# InkTime_Schematic.net
KiCad netlist of a schematic drawn in EAGLE
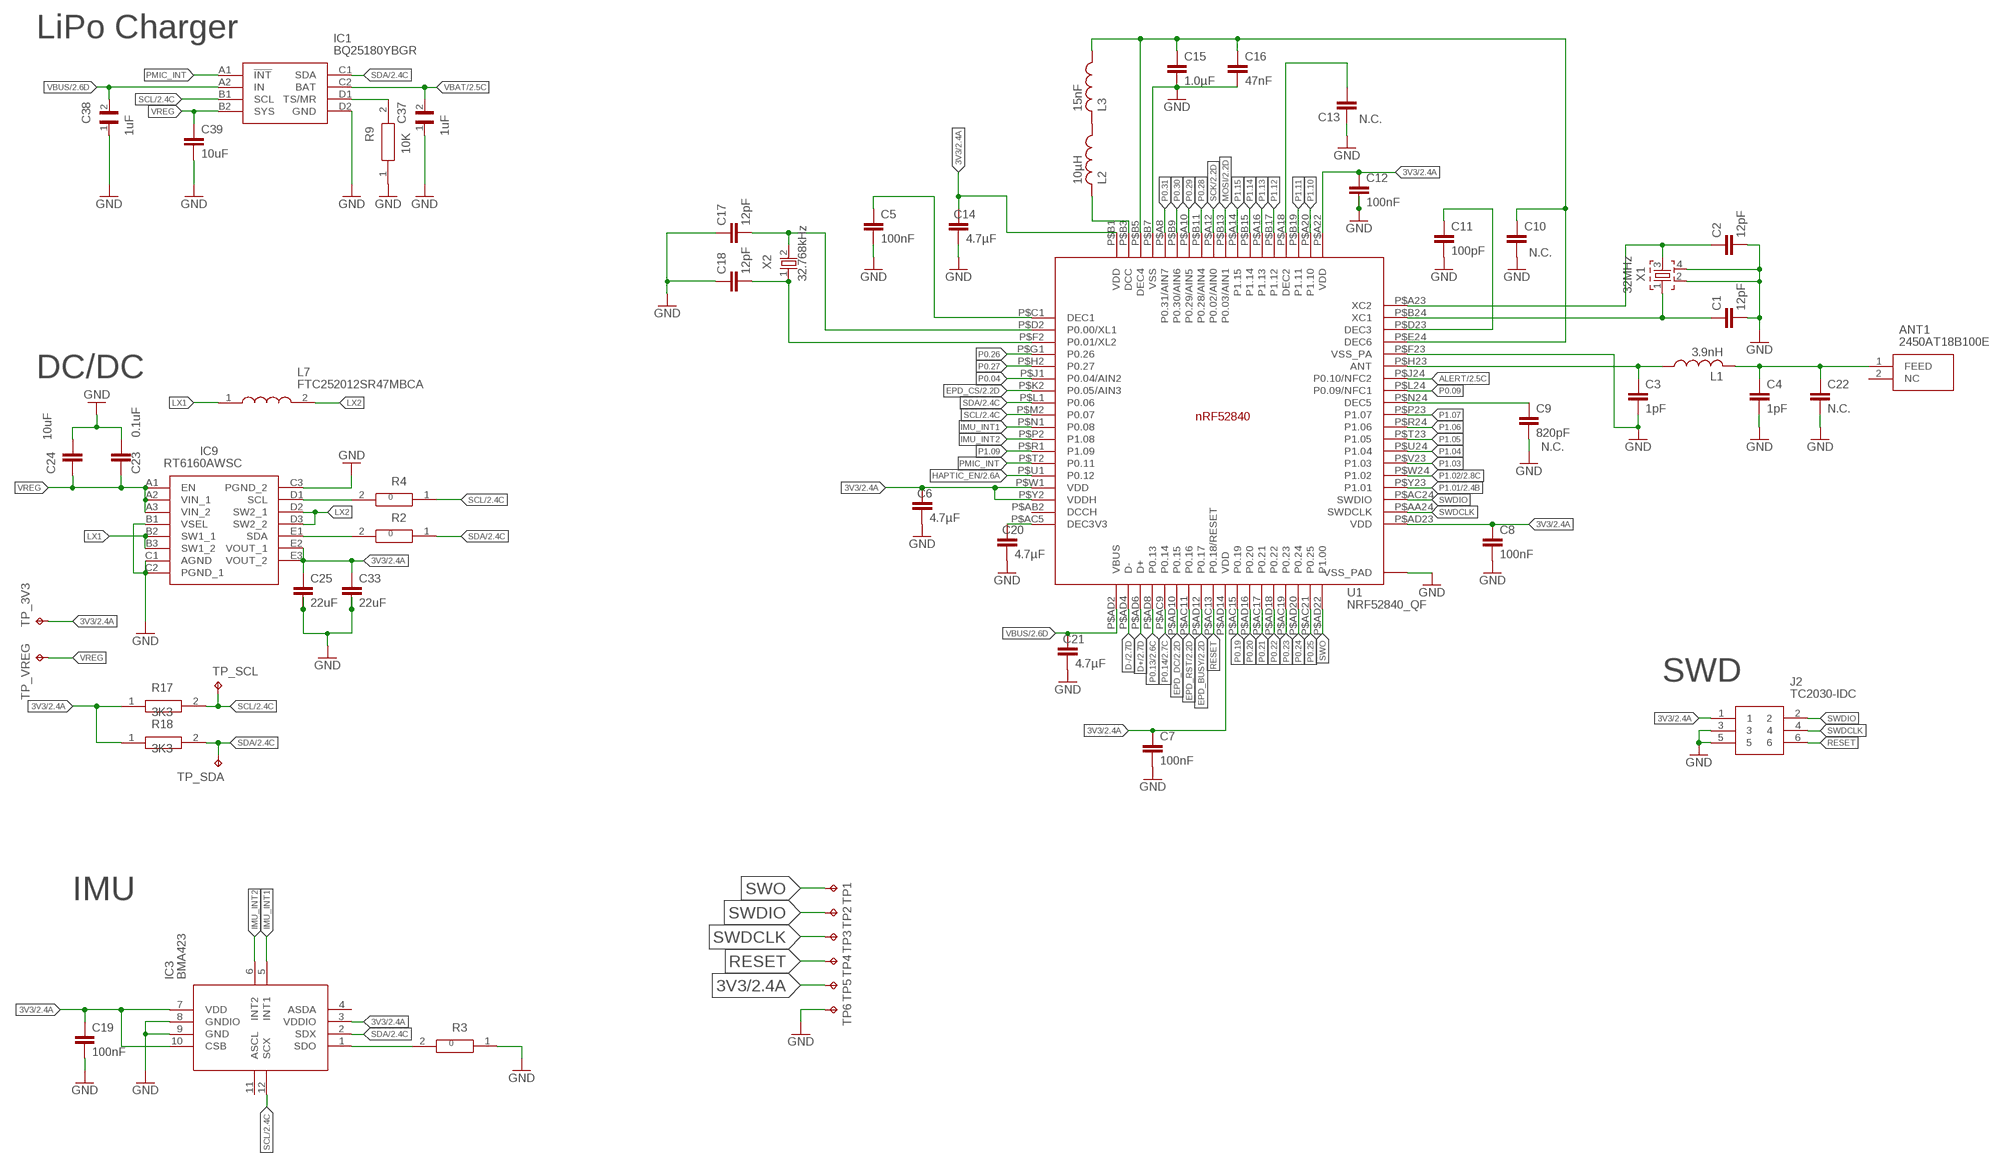
[diagram p0: schematic, sheet 1, part 1 of 2]
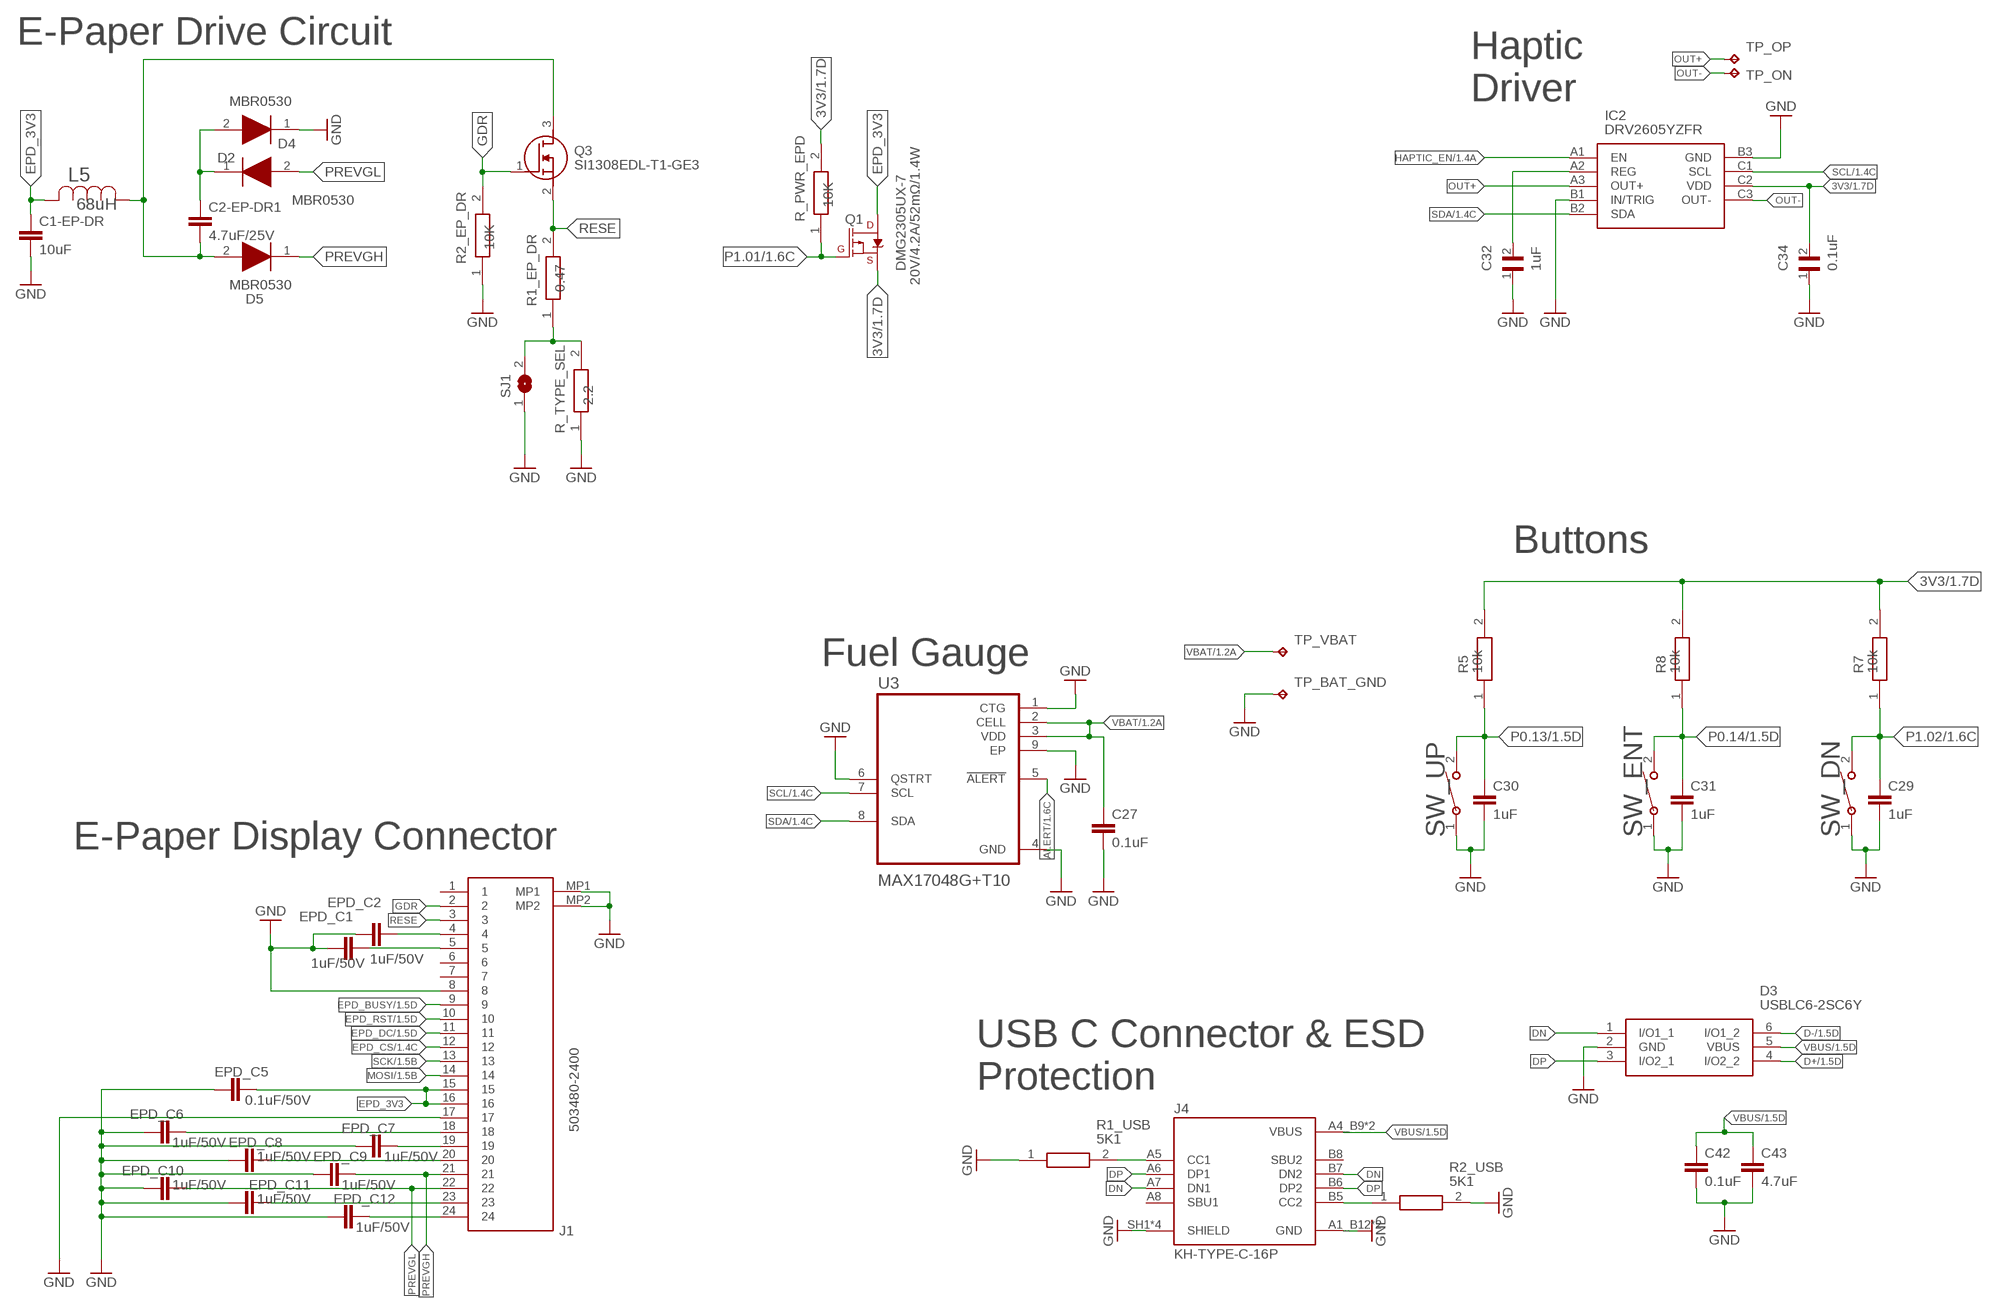
[diagram p1: schematic, sheet 1, part 2 of 2]

(export (version "E")
  (design (tool "Eeschema 10.0.6"))
  (components
    (comp (ref "ANT1")
      (value "2450AT18B100E")
      (footprint "eagle-import:2450AT18B100E_ANTC3216X140N")
      (fields (field (name "MOUSER_PART_NUMBER") "609-2450AT18B100E"))
      (libsource (lib "eagle-import") (part "2450AT18B100E_2450AT18B100E"))
    )
    (comp (ref "C1")
      (value "12pF")
      (footprint "eagle-import:NORDIC_NRF_3_RESC0201_L")
      (libsource (lib "eagle-import") (part "NORDIC_NRF_3_CAPACITOR_0201_L"))
    )
    (comp (ref "C1-EP-DR")
      (value "10uF")
      (footprint "eagle-import:NORDIC_NRF_3_RESC0402_L")
      (libsource (lib "eagle-import") (part "NORDIC_NRF_3_CAPACITOR_0402_L"))
    )
    (comp (ref "C2")
      (value "12pF")
      (footprint "eagle-import:NORDIC_NRF_3_RESC0201_L")
      (libsource (lib "eagle-import") (part "NORDIC_NRF_3_CAPACITOR_0201_L"))
    )
    (comp (ref "C2-EP-DR1")
      (value "4.7uF/25V")
      (footprint "eagle-import:NORDIC_NRF_3_RESC0402_L")
      (libsource (lib "eagle-import") (part "NORDIC_NRF_3_CAPACITOR_0402_L"))
    )
    (comp (ref "C3")
      (value "1pF")
      (footprint "eagle-import:NORDIC_NRF_3_RESC0201_L")
      (libsource (lib "eagle-import") (part "NORDIC_NRF_3_CAPACITOR_0201_L"))
    )
    (comp (ref "C4")
      (value "1pF")
      (footprint "eagle-import:NORDIC_NRF_3_RESC0201_L")
      (libsource (lib "eagle-import") (part "NORDIC_NRF_3_CAPACITOR_0201_L"))
    )
    (comp (ref "C5")
      (value "100nF")
      (footprint "eagle-import:NORDIC_NRF_3_RESC0201_L")
      (libsource (lib "eagle-import") (part "NORDIC_NRF_3_CAPACITOR_0201_L"))
    )
    (comp (ref "C6")
      (value "4.7µF")
      (footprint "eagle-import:NORDIC_NRF_3_RESC0402_L")
      (libsource (lib "eagle-import") (part "NORDIC_NRF_3_CAPACITOR_0402_L"))
    )
    (comp (ref "C7")
      (value "100nF")
      (footprint "eagle-import:NORDIC_NRF_3_RESC0201_L")
      (libsource (lib "eagle-import") (part "NORDIC_NRF_3_CAPACITOR_0201_L"))
    )
    (comp (ref "C8")
      (value "100nF")
      (footprint "eagle-import:NORDIC_NRF_3_RESC0201_L")
      (libsource (lib "eagle-import") (part "NORDIC_NRF_3_CAPACITOR_0201_L"))
    )
    (comp (ref "C9")
      (value "820pF")
      (footprint "eagle-import:NORDIC_NRF_3_RESC0201_L")
      (libsource (lib "eagle-import") (part "NORDIC_NRF_3_CAPACITOR_0201_L"))
    )
    (comp (ref "C10")
      (value "NORDIC_NRF_3_CAPACITOR_0201_L")
      (footprint "eagle-import:NORDIC_NRF_3_RESC0201_L")
      (libsource (lib "eagle-import") (part "NORDIC_NRF_3_CAPACITOR_0201_L"))
    )
    (comp (ref "C11")
      (value "100pF")
      (footprint "eagle-import:NORDIC_NRF_3_RESC0201_L")
      (libsource (lib "eagle-import") (part "NORDIC_NRF_3_CAPACITOR_0201_L"))
    )
    (comp (ref "C12")
      (value "100nF")
      (footprint "eagle-import:NORDIC_NRF_3_RESC0201_L")
      (libsource (lib "eagle-import") (part "NORDIC_NRF_3_CAPACITOR_0201_L"))
    )
    (comp (ref "C13")
      (value "NORDIC_NRF_3_CAPACITOR_0201_L")
      (footprint "eagle-import:NORDIC_NRF_3_RESC0201_L")
      (libsource (lib "eagle-import") (part "NORDIC_NRF_3_CAPACITOR_0201_L"))
    )
    (comp (ref "C14")
      (value "4.7µF")
      (footprint "eagle-import:NORDIC_NRF_3_RESC0402_L")
      (libsource (lib "eagle-import") (part "NORDIC_NRF_3_CAPACITOR_0402_L"))
    )
    (comp (ref "C15")
      (value "1.0µF")
      (footprint "eagle-import:NORDIC_NRF_3_RESC0402_L")
      (libsource (lib "eagle-import") (part "NORDIC_NRF_3_CAPACITOR_0402_L"))
    )
    (comp (ref "C16")
      (value "47nF")
      (footprint "eagle-import:NORDIC_NRF_3_RESC0201_L")
      (libsource (lib "eagle-import") (part "NORDIC_NRF_3_CAPACITOR_0201_L"))
    )
    (comp (ref "C17")
      (value "12pF")
      (footprint "eagle-import:NORDIC_NRF_3_RESC0201_L")
      (libsource (lib "eagle-import") (part "NORDIC_NRF_3_CAPACITOR_0201_L"))
    )
    (comp (ref "C18")
      (value "12pF")
      (footprint "eagle-import:NORDIC_NRF_3_RESC0201_L")
      (libsource (lib "eagle-import") (part "NORDIC_NRF_3_CAPACITOR_0201_L"))
    )
    (comp (ref "C19")
      (value "100nF")
      (footprint "eagle-import:NORDIC_NRF_3_RESC0201_L")
      (libsource (lib "eagle-import") (part "InkTime_v5_vf.fkz7WSyWSr61TWkXU9X4_w_NORDIC_NRF_3_CAPACITOR_0201_L"))
    )
    (comp (ref "C20")
      (value "4.7µF")
      (footprint "eagle-import:NORDIC_NRF_3_RESC0402_L")
      (libsource (lib "eagle-import") (part "NORDIC_NRF_3_CAPACITOR_0402_L"))
    )
    (comp (ref "C21")
      (value "4.7µF")
      (footprint "eagle-import:NORDIC_NRF_3_RESC0402_L")
      (libsource (lib "eagle-import") (part "NORDIC_NRF_3_CAPACITOR_0402_L"))
    )
    (comp (ref "C22")
      (value "N.C.")
      (footprint "eagle-import:NORDIC_NRF_3_RESC0201_L")
      (libsource (lib "eagle-import") (part "NORDIC_NRF_3_CAPACITOR_0201_L"))
    )
    (comp (ref "C23")
      (value "0.1uF")
      (footprint "eagle-import:NORDIC_NRF_3_RESC0201_L")
      (libsource (lib "eagle-import") (part "InkTime_v5_vf.fkz7WSyWSr61TWkXU9X4_w_NORDIC_NRF_3_CAPACITOR_0201_L"))
    )
    (comp (ref "C24")
      (value "10uF")
      (footprint "eagle-import:NORDIC_NRF_3_RESC0402_L")
      (libsource (lib "eagle-import") (part "NORDIC_NRF_3_CAPACITOR_0402_L"))
    )
    (comp (ref "C25")
      (value "22uF")
      (footprint "eagle-import:NORDIC_NRF_3_RESC0402_L")
      (libsource (lib "eagle-import") (part "NORDIC_NRF_3_CAPACITOR_0402_L"))
    )
    (comp (ref "C27")
      (value "0.1uF")
      (footprint "eagle-import:NORDIC_NRF_3_RESC0201_L")
      (libsource (lib "eagle-import") (part "InkTime_v5_vf.fkz7WSyWSr61TWkXU9X4_w_NORDIC_NRF_3_CAPACITOR_0201_L"))
    )
    (comp (ref "C29")
      (value "1uF")
      (footprint "eagle-import:NORDIC_NRF_3_RESC0402_L")
      (libsource (lib "eagle-import") (part "InkTime_v5_vf.fkz7WSyWSr61TWkXU9X4_w_NORDIC_NRF_3_CAPACITOR_0402_L"))
    )
    (comp (ref "C30")
      (value "1uF")
      (footprint "eagle-import:NORDIC_NRF_3_RESC0402_L")
      (libsource (lib "eagle-import") (part "InkTime_v5_vf.fkz7WSyWSr61TWkXU9X4_w_NORDIC_NRF_3_CAPACITOR_0402_L"))
    )
    (comp (ref "C31")
      (value "1uF")
      (footprint "eagle-import:NORDIC_NRF_3_RESC0402_L")
      (libsource (lib "eagle-import") (part "InkTime_v5_vf.fkz7WSyWSr61TWkXU9X4_w_NORDIC_NRF_3_CAPACITOR_0402_L"))
    )
    (comp (ref "C32")
      (value "1uF")
      (footprint "eagle-import:GRM011R60J152KE01L_2_CAPC0201X13N")
      (fields (field (name "MF") "Murata") (field (name "MP") "GRM011R60J152KE01L"))
      (libsource (lib "eagle-import") (part "GRM011R60J152KE01L_2_GRM011R60J152KE01L"))
    )
    (comp (ref "C33")
      (value "22uF")
      (footprint "eagle-import:NORDIC_NRF_3_RESC0402_L")
      (libsource (lib "eagle-import") (part "NORDIC_NRF_3_CAPACITOR_0402_L"))
    )
    (comp (ref "C34")
      (value "0.1uF")
      (footprint "eagle-import:GRM011R60J152KE01L_2_CAPC0201X13N")
      (fields (field (name "MF") "Murata") (field (name "MP") "GRM011R60J152KE01L"))
      (libsource (lib "eagle-import") (part "GRM011R60J152KE01L_2_GRM011R60J152KE01L"))
    )
    (comp (ref "C37")
      (value "1uF")
      (footprint "eagle-import:GRM011R60J152KE01L_2_CAPC0201X13N")
      (fields (field (name "MF") "Murata") (field (name "MP") "GRM011R60J152KE01L"))
      (libsource (lib "eagle-import") (part "GRM011R60J152KE01L_2_GRM011R60J152KE01L"))
    )
    (comp (ref "C38")
      (value "1uF")
      (footprint "eagle-import:GRM011R60J152KE01L_2_CAPC0201X13N")
      (fields (field (name "MF") "Murata") (field (name "MP") "GRM011R60J152KE01L"))
      (libsource (lib "eagle-import") (part "GRM011R60J152KE01L_2_GRM011R60J152KE01L"))
    )
    (comp (ref "C39")
      (value "10uF")
      (footprint "eagle-import:NORDIC_NRF_3_RESC0402_L")
      (libsource (lib "eagle-import") (part "NORDIC_NRF_3_CAPACITOR_0402_L"))
    )
    (comp (ref "C42")
      (value "0.1uF")
      (footprint "eagle-import:NORDIC_NRF_3_RESC0201_L")
      (libsource (lib "eagle-import") (part "InkTime_v5_vf.fkz7WSyWSr61TWkXU9X4_w_NORDIC_NRF_3_CAPACITOR_0201_L"))
    )
    (comp (ref "C43")
      (value "4.7uF")
      (footprint "eagle-import:NORDIC_NRF_3_RESC0402_L")
      (libsource (lib "eagle-import") (part "InkTime_v5_vf.fkz7WSyWSr61TWkXU9X4_w_NORDIC_NRF_3_CAPACITOR_0402_L"))
    )
    (comp (ref "D2")
      (value "MBR0530")
      (footprint "eagle-import:ESP32_C6_LIBRARY_5_SOD3716X135N")
      (fields (field (name "MF") "ON Semiconductor"))
      (libsource (lib "eagle-import") (part "ESP32_C6_LIBRARY_5_MBR0530"))
    )
    (comp (ref "D3")
      (value "USBLC6-2SC6Y")
      (footprint "eagle-import:ESP32_C6_LIBRARY_3_SOT95P280X145-6N")
      (fields (field (name "MF") "STMicroelectronics"))
      (libsource (lib "eagle-import") (part "ESP32_C6_LIBRARY_3_USBLC6-2SC6Y"))
    )
    (comp (ref "D4")
      (value "MBR0530")
      (footprint "eagle-import:ESP32_C6_LIBRARY_5_SOD3716X135N")
      (fields (field (name "MF") "ON Semiconductor"))
      (libsource (lib "eagle-import") (part "ESP32_C6_LIBRARY_5_MBR0530"))
    )
    (comp (ref "D5")
      (value "MBR0530")
      (footprint "eagle-import:ESP32_C6_LIBRARY_5_SOD3716X135N")
      (fields (field (name "MF") "ON Semiconductor"))
      (libsource (lib "eagle-import") (part "ESP32_C6_LIBRARY_5_MBR0530"))
    )
    (comp (ref "EPD_C1")
      (value "1uF/50V")
      (footprint "eagle-import:NORDIC_NRF_3_RESC0402_L")
      (libsource (lib "eagle-import") (part "InkTime_v5_vf.fkz7WSyWSr61TWkXU9X4_w_NORDIC_NRF_3_CAPACITOR_0402_L"))
    )
    (comp (ref "EPD_C2")
      (value "1uF/50V")
      (footprint "eagle-import:NORDIC_NRF_3_RESC0402_L")
      (libsource (lib "eagle-import") (part "InkTime_v5_vf.fkz7WSyWSr61TWkXU9X4_w_NORDIC_NRF_3_CAPACITOR_0402_L"))
    )
    (comp (ref "EPD_C5")
      (value "0.1uF/50V")
      (footprint "eagle-import:NORDIC_NRF_3_RESC0201_L")
      (libsource (lib "eagle-import") (part "InkTime_v5_vf.fkz7WSyWSr61TWkXU9X4_w_NORDIC_NRF_3_CAPACITOR_0201_L"))
    )
    (comp (ref "EPD_C6")
      (value "1uF/50V")
      (footprint "eagle-import:NORDIC_NRF_3_RESC0402_L")
      (libsource (lib "eagle-import") (part "InkTime_v5_vf.fkz7WSyWSr61TWkXU9X4_w_NORDIC_NRF_3_CAPACITOR_0402_L"))
    )
    (comp (ref "EPD_C7")
      (value "1uF/50V")
      (footprint "eagle-import:NORDIC_NRF_3_RESC0402_L")
      (libsource (lib "eagle-import") (part "InkTime_v5_vf.fkz7WSyWSr61TWkXU9X4_w_NORDIC_NRF_3_CAPACITOR_0402_L"))
    )
    (comp (ref "EPD_C8")
      (value "1uF/50V")
      (footprint "eagle-import:NORDIC_NRF_3_RESC0402_L")
      (libsource (lib "eagle-import") (part "InkTime_v5_vf.fkz7WSyWSr61TWkXU9X4_w_NORDIC_NRF_3_CAPACITOR_0402_L"))
    )
    (comp (ref "EPD_C9")
      (value "1uF/50V")
      (footprint "eagle-import:NORDIC_NRF_3_RESC0402_L")
      (libsource (lib "eagle-import") (part "InkTime_v5_vf.fkz7WSyWSr61TWkXU9X4_w_NORDIC_NRF_3_CAPACITOR_0402_L"))
    )
    (comp (ref "EPD_C10")
      (value "1uF/50V")
      (footprint "eagle-import:NORDIC_NRF_3_RESC0402_L")
      (libsource (lib "eagle-import") (part "InkTime_v5_vf.fkz7WSyWSr61TWkXU9X4_w_NORDIC_NRF_3_CAPACITOR_0402_L"))
    )
    (comp (ref "EPD_C11")
      (value "1uF/50V")
      (footprint "eagle-import:NORDIC_NRF_3_RESC0402_L")
      (libsource (lib "eagle-import") (part "InkTime_v5_vf.fkz7WSyWSr61TWkXU9X4_w_NORDIC_NRF_3_CAPACITOR_0402_L"))
    )
    (comp (ref "EPD_C12")
      (value "1uF/50V")
      (footprint "eagle-import:NORDIC_NRF_3_RESC0402_L")
      (libsource (lib "eagle-import") (part "InkTime_v5_vf.fkz7WSyWSr61TWkXU9X4_w_NORDIC_NRF_3_CAPACITOR_0402_L"))
    )
    (comp (ref "IC1")
      (value "BQ25180YBGR")
      (footprint "eagle-import:BQ25180YBGR_BGA8C40P2X4_100X155X50")
      (fields (field (name "MOUSER_PART_NUMBER") "595-BQ25180YBGR"))
      (libsource (lib "eagle-import") (part "BQ25180YBGR_BQ25180YBGR"))
    )
    (comp (ref "IC2")
      (value "DRV2605YZFR")
      (footprint "eagle-import:DRV2605YZFR_BGA9C50P3X3_144X144X62")
      (libsource (lib "eagle-import") (part "DRV2605YZFR_DRV2605YZFR"))
    )
    (comp (ref "IC3")
      (value "BMA423")
      (footprint "eagle-import:BMA423_BMA423")
      (fields (field (name "MOUSER_PART_NUMBER") "262-BMA423"))
      (libsource (lib "eagle-import") (part "BMA423_BMA423"))
    )
    (comp (ref "IC9")
      (value "RT6160AWSC")
      (footprint "eagle-import:RT6160AWSC_BGA15C40P3X5_140X230X60")
      (fields (field (name "MOUSER_PART_NUMBER") "835-RT6160AWSC"))
      (libsource (lib "eagle-import") (part "RT6160AWSC_RT6160AWSC"))
    )
    (comp (ref "J1")
      (value "503480-2400")
      (footprint "eagle-import:503480-2400_5034802400")
      (fields (field (name "MOUSER_PART_NUMBER") "538-503480-2400"))
      (libsource (lib "eagle-import") (part "503480-2400_503480-2400"))
    )
    (comp (ref "J2")
      (value "TC2030-IDC")
      (footprint "eagle-import:TC2030-IDC_TC2030IDC")
      (libsource (lib "eagle-import") (part "TC2030-IDC_TC2030-IDC"))
    )
    (comp (ref "J4")
      (value "KH-TYPE-C-16P")
      (footprint "eagle-import:KH-TYPE-C-16P_KINGHELM_KH-TYPE-C-16P")
      (fields (field (name "MF") "kinghelm"))
      (libsource (lib "eagle-import") (part "KH-TYPE-C-16P_KH-TYPE-C-16P"))
    )
    (comp (ref "L1")
      (value "3.9nH")
      (footprint "eagle-import:NORDIC_NRF_2_RESC0402_L")
      (libsource (lib "eagle-import") (part "InkTime_v5_vf.fkz7WSyWSr61TWkXU9X4_w_NORDIC_NRF_2_INDUCTOR_0402_L"))
    )
    (comp (ref "L2")
      (value "10µH")
      (footprint "eagle-import:NORDIC_NRF_2_RESC0402_L")
      (libsource (lib "eagle-import") (part "NORDIC_NRF_2_INDUCTOR_0402_L"))
    )
    (comp (ref "L3")
      (value "15nF")
      (footprint "eagle-import:NORDIC_NRF_2_RESC0402_L")
      (libsource (lib "eagle-import") (part "NORDIC_NRF_2_INDUCTOR_0402_L"))
    )
    (comp (ref "L5")
      (value "68uH")
      (footprint "eagle-import:ESP32_C6_LIBRARY_2_IND_4828-WE-TPC_WRE")
      (fields
        (field (name "MANUFACTURER_PART_NUMBER") "744043680")
        (field (name "COPYRIGHT") "Copyright (C) 2024 Ultra Librarian. All rights reserved.")
      )
      (libsource (lib "eagle-import") (part "ESP32_C6_LIBRARY_2_744043680IND_4828-WE-TPC_WRE"))
    )
    (comp (ref "L7")
      (value "FTC252012SR47MBCA")
      (footprint "eagle-import:MLP2016SR47MT0S1_INDC2016X100N")
      (libsource (lib "eagle-import") (part "MLP2016SR47MT0S1_FTC252012SR47MBCA"))
    )
    (comp (ref "Q1")
      (value "20V/4.2A/52mΩ/1.4W")
      (footprint "eagle-import:ESP32_C6_LIBRARY_4_ESP32_C6_LIBRARY_4_ESP32_C6_LIBRARY_4_ESP32_C6_LIBRARY_4_ESP32_WROVER_SPARKFUN-DISCRETESEMI_SOT23-3")
      (libsource (lib "eagle-import") (part "ESP32_C6_LIBRARY_4_ESP32_WROVER_SPARKFUN-DISCRETESEMI_MOSFET_PCH-DMG2305UX-7"))
    )
    (comp (ref "Q3")
      (value "SI1308EDL-T1-GE3")
      (footprint "eagle-import:ESP32_C6_LIBRARY_6_SOT65P210X110-3N")
      (fields (field (name "MF") "Vishay Siliconix"))
      (libsource (lib "eagle-import") (part "ESP32_C6_LIBRARY_6_SI1308EDL-T1-GE3"))
    )
    (comp (ref "R1_EP_DR")
      (value "0.47")
      (footprint "eagle-import:CPF0201D7K68C1_0201")
      (libsource (lib "eagle-import") (part "CPF0201D7K68C1_CPF0201D7K68C1"))
    )
    (comp (ref "R1_USB")
      (value "5K1")
      (footprint "eagle-import:ERA-1AEB3401C_0201")
      (libsource (lib "eagle-import") (part "ERA-1AEB3401C_CPF0201D7K68C1"))
    )
    (comp (ref "R2")
      (value "CPF0201D7K68C1_CPF0201D7K68C1")
      (footprint "eagle-import:CPF0201D7K68C1_0201")
      (libsource (lib "eagle-import") (part "CPF0201D7K68C1_CPF0201D7K68C1"))
    )
    (comp (ref "R2_EP_DR")
      (value "10K")
      (footprint "eagle-import:CPF0201D7K68C1_0201")
      (libsource (lib "eagle-import") (part "CPF0201D7K68C1_CPF0201D7K68C1"))
    )
    (comp (ref "R2_USB")
      (value "5K1")
      (footprint "eagle-import:ERA-1AEB3401C_0201")
      (libsource (lib "eagle-import") (part "ERA-1AEB3401C_CPF0201D7K68C1"))
    )
    (comp (ref "R3")
      (value "CPF0201D7K68C1_CPF0201D7K68C1")
      (footprint "eagle-import:CPF0201D7K68C1_0201")
      (libsource (lib "eagle-import") (part "CPF0201D7K68C1_CPF0201D7K68C1"))
    )
    (comp (ref "R4")
      (value "CPF0201D7K68C1_CPF0201D7K68C1")
      (footprint "eagle-import:CPF0201D7K68C1_0201")
      (libsource (lib "eagle-import") (part "CPF0201D7K68C1_CPF0201D7K68C1"))
    )
    (comp (ref "R5")
      (value "10k")
      (footprint "eagle-import:CPF0201D7K68C1_0201")
      (libsource (lib "eagle-import") (part "InkTime_v5_vf.fkz7WSyWSr61TWkXU9X4_w_CPF0201D7K68C1_CPF0201D7K68C1"))
    )
    (comp (ref "R7")
      (value "10k")
      (footprint "eagle-import:CPF0201D7K68C1_0201")
      (libsource (lib "eagle-import") (part "InkTime_v5_vf.fkz7WSyWSr61TWkXU9X4_w_CPF0201D7K68C1_CPF0201D7K68C1"))
    )
    (comp (ref "R8")
      (value "10k")
      (footprint "eagle-import:CPF0201D7K68C1_0201")
      (libsource (lib "eagle-import") (part "InkTime_v5_vf.fkz7WSyWSr61TWkXU9X4_w_CPF0201D7K68C1_CPF0201D7K68C1"))
    )
    (comp (ref "R9")
      (value "10K")
      (footprint "eagle-import:CPF0201D7K68C1_0201")
      (libsource (lib "eagle-import") (part "CPF0201D7K68C1_CPF0201D7K68C1"))
    )
    (comp (ref "R17")
      (value "3K3")
      (footprint "eagle-import:CPF0201D7K68C1_0201")
      (libsource (lib "eagle-import") (part "CPF0201D7K68C1_CPF0201D7K68C1"))
    )
    (comp (ref "R18")
      (value "3K3")
      (footprint "eagle-import:CPF0201D7K68C1_0201")
      (libsource (lib "eagle-import") (part "CPF0201D7K68C1_CPF0201D7K68C1"))
    )
    (comp (ref "R_PWR_EPD")
      (value "10K")
      (footprint "eagle-import:CPF0201D7K68C1_0201")
      (libsource (lib "eagle-import") (part "CPF0201D7K68C1_CPF0201D7K68C1"))
    )
    (comp (ref "R_TYPE_SEL")
      (value "2.2")
      (footprint "eagle-import:CPF0201D7K68C1_0201")
      (libsource (lib "eagle-import") (part "CPF0201D7K68C1_CPF0201D7K68C1"))
    )
    (comp (ref "SJ1")
      (value "ESP32_C6_LIBRARY_7_JUMPER_SJ")
      (footprint "eagle-import:ESP32_C6_LIBRARY_7_JUMPER_SJ")
      (libsource (lib "eagle-import") (part "ESP32_C6_LIBRARY_7_JUMPER_SJ"))
    )
    (comp (ref "SW_DN")
      (value "2025-10-22_07-23-44_LIBRARY_EVP-AKE31ASW_EVP-AKE31A_PAN")
      (footprint "eagle-import:2025-10-22_07-23-44_LIBRARY_SW_EVP-AKE31A_PAN")
      (fields
        (field (name "MANUFACTURER_PART_NUMBER") "EVP-AKE31A")
        (field (name "COPYRIGHT") "Copyright (C) 2025 Ultra Librarian. All rights reserved.")
      )
      (libsource (lib "eagle-import") (part "2025-10-22_07-23-44_LIBRARY_EVP-AKE31ASW_EVP-AKE31A_PAN"))
    )
    (comp (ref "SW_ENT")
      (value "SW_ENT")
      (footprint "eagle-import:2025-10-22_07-23-44_LIBRARY_SW_EVP-AKE31A_PAN")
      (fields
        (field (name "MANUFACTURER_PART_NUMBER") "EVP-AKE31A")
        (field (name "COPYRIGHT") "Copyright (C) 2025 Ultra Librarian. All rights reserved.")
      )
      (libsource (lib "eagle-import") (part "2025-10-22_07-23-44_LIBRARY_EVP-AKE31ASW_EVP-AKE31A_PAN"))
    )
    (comp (ref "SW_UP")
      (value "2025-10-22_07-23-44_LIBRARY_EVP-AKE31ASW_EVP-AKE31A_PAN")
      (footprint "eagle-import:2025-10-22_07-23-44_LIBRARY_SW_EVP-AKE31A_PAN")
      (fields
        (field (name "MANUFACTURER_PART_NUMBER") "EVP-AKE31A")
        (field (name "COPYRIGHT") "Copyright (C) 2025 Ultra Librarian. All rights reserved.")
      )
      (libsource (lib "eagle-import") (part "2025-10-22_07-23-44_LIBRARY_EVP-AKE31ASW_EVP-AKE31A_PAN"))
    )
    (comp (ref "TP1")
      (value "HECTOR_WATCH_1_TPTP20R")
      (footprint "eagle-import:HECTOR_WATCH_1_TP20R")
      (libsource (lib "eagle-import") (part "HECTOR_WATCH_1_TPTP20R"))
    )
    (comp (ref "TP2")
      (value "HECTOR_WATCH_1_TPTP20R")
      (footprint "eagle-import:HECTOR_WATCH_1_TP20R")
      (libsource (lib "eagle-import") (part "HECTOR_WATCH_1_TPTP20R"))
    )
    (comp (ref "TP3")
      (value "HECTOR_WATCH_1_TPTP20R")
      (footprint "eagle-import:HECTOR_WATCH_1_TP20R")
      (libsource (lib "eagle-import") (part "HECTOR_WATCH_1_TPTP20R"))
    )
    (comp (ref "TP4")
      (value "HECTOR_WATCH_1_TPTP20R")
      (footprint "eagle-import:HECTOR_WATCH_1_TP20R")
      (libsource (lib "eagle-import") (part "HECTOR_WATCH_1_TPTP20R"))
    )
    (comp (ref "TP5")
      (value "HECTOR_WATCH_1_TPTP20R")
      (footprint "eagle-import:HECTOR_WATCH_1_TP20R")
      (libsource (lib "eagle-import") (part "HECTOR_WATCH_1_TPTP20R"))
    )
    (comp (ref "TP6")
      (value "HECTOR_WATCH_1_TPTP20R")
      (footprint "eagle-import:HECTOR_WATCH_1_TP20R")
      (libsource (lib "eagle-import") (part "HECTOR_WATCH_1_TPTP20R"))
    )
    (comp (ref "TP_3V3")
      (value "HECTOR_WATCH_1_TPTP20R")
      (footprint "eagle-import:HECTOR_WATCH_1_TP20R")
      (libsource (lib "eagle-import") (part "HECTOR_WATCH_1_TPTP20R"))
    )
    (comp (ref "TP_BAT_GND")
      (value "HECTOR_WATCH_1_TPTP20R")
      (footprint "eagle-import:HECTOR_WATCH_1_TP20R")
      (libsource (lib "eagle-import") (part "InkTime_v5_vf.fkz7WSyWSr61TWkXU9X4_w_HECTOR_WATCH_1_TPTP20R"))
    )
    (comp (ref "TP_ON")
      (value "HECTOR_WATCH_1_TPTP20R")
      (footprint "eagle-import:HECTOR_WATCH_1_TP20R")
      (libsource (lib "eagle-import") (part "HECTOR_WATCH_1_TPTP20R"))
    )
    (comp (ref "TP_OP")
      (value "HECTOR_WATCH_1_TPTP20R")
      (footprint "eagle-import:HECTOR_WATCH_1_TP20R")
      (libsource (lib "eagle-import") (part "HECTOR_WATCH_1_TPTP20R"))
    )
    (comp (ref "TP_SCL")
      (value "HECTOR_WATCH_1_TPTP20R")
      (footprint "eagle-import:HECTOR_WATCH_1_TP20R")
      (libsource (lib "eagle-import") (part "HECTOR_WATCH_1_TPTP20R"))
    )
    (comp (ref "TP_SDA")
      (value "HECTOR_WATCH_1_TPTP20R")
      (footprint "eagle-import:HECTOR_WATCH_1_TP20R")
      (libsource (lib "eagle-import") (part "HECTOR_WATCH_1_TPTP20R"))
    )
    (comp (ref "TP_VBAT")
      (value "HECTOR_WATCH_1_TPTP20R")
      (footprint "eagle-import:HECTOR_WATCH_1_TP20R")
      (libsource (lib "eagle-import") (part "InkTime_v5_vf.fkz7WSyWSr61TWkXU9X4_w_HECTOR_WATCH_1_TPTP20R"))
    )
    (comp (ref "TP_VREG")
      (value "HECTOR_WATCH_1_TPTP20R")
      (footprint "eagle-import:HECTOR_WATCH_1_TP20R")
      (libsource (lib "eagle-import") (part "HECTOR_WATCH_1_TPTP20R"))
    )
    (comp (ref "U1")
      (value "NRF52840_QF")
      (footprint "eagle-import:NORDIC_NRF_4_AQFN50P700X700X85_HS-74N")
      (libsource (lib "eagle-import") (part "NORDIC_NRF_4_NRF52840_QF"))
    )
    (comp (ref "U3")
      (value "MAX17048G+T10")
      (footprint "eagle-import:ESP32_C6_LIBRARY_SON50P200X200X80-9N")
      (fields (field (name "MF") "Analog Devices"))
      (libsource (lib "eagle-import") (part "ESP32_C6_LIBRARY_MAX17048G+T10"))
    )
    (comp (ref "X1")
      (value "32MHz")
      (footprint "eagle-import:NORDIC_NRF_BT-XTAL_2016_N")
      (libsource (lib "eagle-import") (part "NORDIC_NRF_XTAL_32MHZ"))
    )
    (comp (ref "X2")
      (value "32.768kHz")
      (footprint "eagle-import:NORDIC_NRF_1_XTAL_3215_N")
      (libsource (lib "eagle-import") (part "NORDIC_NRF_1_XTAL_32KHZ"))
    )
  )
  (nets
    (net (code "1") (name "3V3{slash}1.7D") (class "Default")
      (node (ref "C34") (pin "2") (pinfunction "2_2") (pintype "passive"))
      (node (ref "IC2") (pin "C2") (pinfunction "VDD_C2") (pintype "bidirectional"))
      (node (ref "Q1") (pin "2") (pinfunction "S_2") (pintype "bidirectional"))
      (node (ref "R5") (pin "2") (pinfunction "2_2") (pintype "bidirectional"))
      (node (ref "R7") (pin "2") (pinfunction "2_2") (pintype "bidirectional"))
      (node (ref "R8") (pin "2") (pinfunction "2_2") (pintype "bidirectional"))
      (node (ref "R_PWR_EPD") (pin "2") (pinfunction "2_2") (pintype "bidirectional"))
    )
    (net (code "2") (name "3V3{slash}2.4A") (class "Default")
      (node (ref "C12") (pin "1") (pinfunction "1_1") (pintype "passive"))
      (node (ref "C14") (pin "1") (pinfunction "1_1") (pintype "passive"))
      (node (ref "C19") (pin "1") (pinfunction "1_1") (pintype "passive"))
      (node (ref "C25") (pin "1") (pinfunction "1_1") (pintype "passive"))
      (node (ref "C33") (pin "1") (pinfunction "1_1") (pintype "passive"))
      (node (ref "C6") (pin "1") (pinfunction "1_1") (pintype "passive"))
      (node (ref "C7") (pin "1") (pinfunction "1_1") (pintype "passive"))
      (node (ref "C8") (pin "1") (pinfunction "1_1") (pintype "passive"))
      (node (ref "IC3") (pin "10") (pinfunction "CSB_10") (pintype "bidirectional"))
      (node (ref "IC3") (pin "3") (pinfunction "VDDIO_3") (pintype "bidirectional"))
      (node (ref "IC3") (pin "7") (pinfunction "VDD_7") (pintype "bidirectional"))
      (node (ref "IC9") (pin "E2") (pinfunction "VOUT_1_E2") (pintype "bidirectional"))
      (node (ref "IC9") (pin "E3") (pinfunction "VOUT_2_E3") (pintype "bidirectional"))
      (node (ref "J2") (pin "1") (pinfunction "1_1") (pintype "bidirectional"))
      (node (ref "R17") (pin "1") (pinfunction "1_1") (pintype "bidirectional"))
      (node (ref "R18") (pin "1") (pinfunction "1_1") (pintype "bidirectional"))
      (node (ref "TP5") (pin "TP") (pinfunction "TP_TP") (pintype "input"))
      (node (ref "TP_3V3") (pin "TP") (pinfunction "TP_TP") (pintype "input"))
      (node (ref "U1") (pin "P$A22") (pinfunction "VDD_P$A22") (pintype "power_in"))
      (node (ref "U1") (pin "P$AD14") (pinfunction "VDD_P$AD14") (pintype "power_in"))
      (node (ref "U1") (pin "P$AD23") (pinfunction "VDD_P$AD23") (pintype "power_in"))
      (node (ref "U1") (pin "P$B1") (pinfunction "VDD_P$B1") (pintype "power_in"))
      (node (ref "U1") (pin "P$W1") (pinfunction "VDD_P$W1") (pintype "power_in"))
      (node (ref "U1") (pin "P$Y2") (pinfunction "VDDH_P$Y2") (pintype "power_in"))
    )
    (net (code "3") (name "ALERT{slash}1.6C") (class "Default")
      (node (ref "U3") (pin "5") (pinfunction "~{ALERT}_5") (pintype "output"))
    )
    (net (code "4") (name "ALERT{slash}2.5C") (class "Default")
      (node (ref "U1") (pin "P$J24") (pinfunction "P0.10/NFC2_P$J24") (pintype "bidirectional"))
    )
    (net (code "5") (name "D+{slash}1.5D") (class "Default")
      (node (ref "D3") (pin "4") (pinfunction "I/O2_2_4") (pintype "bidirectional"))
    )
    (net (code "6") (name "D+{slash}2.7D") (class "Default")
      (node (ref "U1") (pin "P$AD6") (pinfunction "D+_P$AD6") (pintype "bidirectional"))
    )
    (net (code "7") (name "D-{slash}1.5D") (class "Default")
      (node (ref "D3") (pin "6") (pinfunction "I/O1_2_6") (pintype "bidirectional"))
    )
    (net (code "8") (name "D-{slash}2.7D") (class "Default")
      (node (ref "U1") (pin "P$AD4") (pinfunction "D-_P$AD4") (pintype "bidirectional"))
    )
    (net (code "9") (name "DN") (class "Default")
      (node (ref "D3") (pin "1") (pinfunction "I/O1_1_1") (pintype "bidirectional"))
      (node (ref "J4") (pin "A7") (pinfunction "DN1_A7") (pintype "bidirectional"))
      (node (ref "J4") (pin "B7") (pinfunction "DN2_B7") (pintype "bidirectional"))
    )
    (net (code "10") (name "DP") (class "Default")
      (node (ref "D3") (pin "3") (pinfunction "I/O2_1_3") (pintype "bidirectional"))
      (node (ref "J4") (pin "A6") (pinfunction "DP1_A6") (pintype "bidirectional"))
      (node (ref "J4") (pin "B6") (pinfunction "DP2_B6") (pintype "bidirectional"))
    )
    (net (code "11") (name "EPD_3V3") (class "Default")
      (node (ref "C1-EP-DR") (pin "1") (pinfunction "1_1") (pintype "passive"))
      (node (ref "EPD_C5") (pin "2") (pinfunction "2_2") (pintype "passive"))
      (node (ref "J1") (pin "15") (pinfunction "15_15") (pintype "bidirectional"))
      (node (ref "J1") (pin "16") (pinfunction "16_16") (pintype "bidirectional"))
      (node (ref "L5") (pin "2") (pinfunction "2_2") (pintype "passive"))
      (node (ref "Q1") (pin "3") (pinfunction "D_3") (pintype "bidirectional"))
    )
    (net (code "12") (name "EPD_BUSY{slash}1.5D") (class "Default")
      (node (ref "J1") (pin "9") (pinfunction "9_9") (pintype "bidirectional"))
    )
    (net (code "13") (name "EPD_BUSY{slash}2.2D") (class "Default")
      (node (ref "U1") (pin "P$AD12") (pinfunction "P0.17_P$AD12") (pintype "bidirectional"))
    )
    (net (code "14") (name "EPD_CS{slash}1.4C") (class "Default")
      (node (ref "J1") (pin "12") (pinfunction "12_12") (pintype "bidirectional"))
    )
    (net (code "15") (name "EPD_CS{slash}2.2D") (class "Default")
      (node (ref "U1") (pin "P$K2") (pinfunction "P0.05/AIN3_P$K2") (pintype "bidirectional"))
    )
    (net (code "16") (name "EPD_DC{slash}1.5D") (class "Default")
      (node (ref "J1") (pin "11") (pinfunction "11_11") (pintype "bidirectional"))
    )
    (net (code "17") (name "EPD_DC{slash}2.2D") (class "Default")
      (node (ref "U1") (pin "P$AD10") (pinfunction "P0.15_P$AD10") (pintype "bidirectional"))
    )
    (net (code "18") (name "EPD_RST{slash}1.5D") (class "Default")
      (node (ref "J1") (pin "10") (pinfunction "10_10") (pintype "bidirectional"))
    )
    (net (code "19") (name "EPD_RST{slash}2.2D") (class "Default")
      (node (ref "U1") (pin "P$AC11") (pinfunction "P0.16_P$AC11") (pintype "bidirectional"))
    )
    (net (code "20") (name "GDR") (class "Default")
      (node (ref "J1") (pin "2") (pinfunction "2_2") (pintype "bidirectional"))
      (node (ref "Q3") (pin "1") (pinfunction "G_1") (pintype "bidirectional"))
      (node (ref "R2_EP_DR") (pin "2") (pinfunction "2_2") (pintype "bidirectional"))
    )
    (net (code "21") (name "GND") (class "Default")
      (node (ref "C1") (pin "2") (pinfunction "2_2") (pintype "passive"))
      (node (ref "C1-EP-DR") (pin "2") (pinfunction "2_2") (pintype "passive"))
      (node (ref "C10") (pin "1") (pinfunction "1_1") (pintype "passive"))
      (node (ref "C11") (pin "2") (pinfunction "2_2") (pintype "passive"))
      (node (ref "C12") (pin "2") (pinfunction "2_2") (pintype "passive"))
      (node (ref "C13") (pin "1") (pinfunction "1_1") (pintype "passive"))
      (node (ref "C14") (pin "2") (pinfunction "2_2") (pintype "passive"))
      (node (ref "C15") (pin "2") (pinfunction "2_2") (pintype "passive"))
      (node (ref "C16") (pin "2") (pinfunction "2_2") (pintype "passive"))
      (node (ref "C17") (pin "1") (pinfunction "1_1") (pintype "passive"))
      (node (ref "C18") (pin "1") (pinfunction "1_1") (pintype "passive"))
      (node (ref "C19") (pin "2") (pinfunction "2_2") (pintype "passive"))
      (node (ref "C2") (pin "2") (pinfunction "2_2") (pintype "passive"))
      (node (ref "C20") (pin "2") (pinfunction "2_2") (pintype "passive"))
      (node (ref "C21") (pin "2") (pinfunction "2_2") (pintype "passive"))
      (node (ref "C22") (pin "2") (pinfunction "2_2") (pintype "passive"))
      (node (ref "C23") (pin "1") (pinfunction "1_1") (pintype "passive"))
      (node (ref "C24") (pin "1") (pinfunction "1_1") (pintype "passive"))
      (node (ref "C25") (pin "2") (pinfunction "2_2") (pintype "passive"))
      (node (ref "C27") (pin "2") (pinfunction "2_2") (pintype "passive"))
      (node (ref "C29") (pin "2") (pinfunction "2_2") (pintype "passive"))
      (node (ref "C3") (pin "2") (pinfunction "2_2") (pintype "passive"))
      (node (ref "C30") (pin "2") (pinfunction "2_2") (pintype "passive"))
      (node (ref "C31") (pin "2") (pinfunction "2_2") (pintype "passive"))
      (node (ref "C32") (pin "1") (pinfunction "1_1") (pintype "passive"))
      (node (ref "C33") (pin "2") (pinfunction "2_2") (pintype "passive"))
      (node (ref "C34") (pin "1") (pinfunction "1_1") (pintype "passive"))
      (node (ref "C37") (pin "1") (pinfunction "1_1") (pintype "passive"))
      (node (ref "C38") (pin "1") (pinfunction "1_1") (pintype "passive"))
      (node (ref "C39") (pin "2") (pinfunction "2_2") (pintype "passive"))
      (node (ref "C4") (pin "2") (pinfunction "2_2") (pintype "passive"))
      (node (ref "C42") (pin "2") (pinfunction "2_2") (pintype "passive"))
      (node (ref "C43") (pin "2") (pinfunction "2_2") (pintype "passive"))
      (node (ref "C5") (pin "2") (pinfunction "2_2") (pintype "passive"))
      (node (ref "C6") (pin "2") (pinfunction "2_2") (pintype "passive"))
      (node (ref "C7") (pin "2") (pinfunction "2_2") (pintype "passive"))
      (node (ref "C8") (pin "2") (pinfunction "2_2") (pintype "passive"))
      (node (ref "C9") (pin "2") (pinfunction "2_2") (pintype "passive"))
      (node (ref "D2") (pin "1") (pinfunction "K_1") (pintype "bidirectional"))
      (node (ref "D3") (pin "2") (pinfunction "GND_2") (pintype "bidirectional"))
      (node (ref "EPD_C1") (pin "1") (pinfunction "1_1") (pintype "passive"))
      (node (ref "EPD_C10") (pin "1") (pinfunction "1_1") (pintype "passive"))
      (node (ref "EPD_C11") (pin "1") (pinfunction "1_1") (pintype "passive"))
      (node (ref "EPD_C12") (pin "1") (pinfunction "1_1") (pintype "passive"))
      (node (ref "EPD_C2") (pin "1") (pinfunction "1_1") (pintype "passive"))
      (node (ref "EPD_C5") (pin "1") (pinfunction "1_1") (pintype "passive"))
      (node (ref "EPD_C6") (pin "1") (pinfunction "1_1") (pintype "passive"))
      (node (ref "EPD_C7") (pin "1") (pinfunction "1_1") (pintype "passive"))
      (node (ref "EPD_C8") (pin "1") (pinfunction "1_1") (pintype "passive"))
      (node (ref "EPD_C9") (pin "1") (pinfunction "1_1") (pintype "passive"))
      (node (ref "IC1") (pin "D2") (pinfunction "GND_D2") (pintype "bidirectional"))
      (node (ref "IC2") (pin "B1") (pinfunction "IN/TRIG_B1") (pintype "bidirectional"))
      (node (ref "IC2") (pin "B3") (pinfunction "GND_B3") (pintype "bidirectional"))
      (node (ref "IC3") (pin "8") (pinfunction "GNDIO_8") (pintype "bidirectional"))
      (node (ref "IC3") (pin "9") (pinfunction "GND_9") (pintype "bidirectional"))
      (node (ref "IC9") (pin "B1") (pinfunction "VSEL_B1") (pintype "bidirectional"))
      (node (ref "IC9") (pin "C1") (pinfunction "AGND_C1") (pintype "bidirectional"))
      (node (ref "IC9") (pin "C2") (pinfunction "PGND_1_C2") (pintype "bidirectional"))
      (node (ref "IC9") (pin "C3") (pinfunction "PGND_2_C3") (pintype "bidirectional"))
      (node (ref "J1") (pin "17") (pinfunction "17_17") (pintype "bidirectional"))
      (node (ref "J1") (pin "8") (pinfunction "8_8") (pintype "bidirectional"))
      (node (ref "J1") (pin "MP1") (pinfunction "MP1_MP1") (pintype "bidirectional"))
      (node (ref "J1") (pin "MP2") (pinfunction "MP2_MP2") (pintype "bidirectional"))
      (node (ref "J2") (pin "3") (pinfunction "3_3") (pintype "bidirectional"))
      (node (ref "J2") (pin "5") (pinfunction "5_5") (pintype "bidirectional"))
      (node (ref "J4") (pin "A12_B1") (pinfunction "GND_A12_B1") (pintype "power_in"))
      (node (ref "J4") (pin "A1_B12") (pinfunction "GND_A1_B12") (pintype "power_in"))
      (node (ref "J4") (pin "SH1") (pinfunction "SHIELD_SH1") (pintype "passive"))
      (node (ref "J4") (pin "SH2") (pinfunction "SHIELD_SH2") (pintype "passive"))
      (node (ref "J4") (pin "SH3") (pinfunction "SHIELD_SH3") (pintype "passive"))
      (node (ref "J4") (pin "SH4") (pinfunction "SHIELD_SH4") (pintype "passive"))
      (node (ref "R1_USB") (pin "1") (pinfunction "1_1") (pintype "bidirectional"))
      (node (ref "R2_EP_DR") (pin "1") (pinfunction "1_1") (pintype "bidirectional"))
      (node (ref "R2_USB") (pin "2") (pinfunction "2_2") (pintype "bidirectional"))
      (node (ref "R3") (pin "1") (pinfunction "1_1") (pintype "bidirectional"))
      (node (ref "R9") (pin "1") (pinfunction "1_1") (pintype "bidirectional"))
      (node (ref "R_TYPE_SEL") (pin "1") (pinfunction "1_1") (pintype "bidirectional"))
      (node (ref "SJ1") (pin "1") (pinfunction "1_1") (pintype "passive"))
      (node (ref "SW_DN") (pin "1") (pinfunction "1_1") (pintype "passive"))
      (node (ref "SW_ENT") (pin "1") (pinfunction "1_1") (pintype "passive"))
      (node (ref "SW_UP") (pin "1") (pinfunction "1_1") (pintype "passive"))
      (node (ref "TP6") (pin "TP") (pinfunction "TP_TP") (pintype "input"))
      (node (ref "TP_BAT_GND") (pin "TP") (pinfunction "TP_TP") (pintype "input"))
      (node (ref "U1") (pin "P$74") (pinfunction "VSS_PAD_P$74") (pintype "bidirectional"))
      (node (ref "U1") (pin "P$75") (pinfunction "VSS_PAD_P$75") (pintype "bidirectional"))
      (node (ref "U1") (pin "P$76") (pinfunction "VSS_PAD_P$76") (pintype "bidirectional"))
      (node (ref "U1") (pin "P$77") (pinfunction "VSS_PAD_P$77") (pintype "bidirectional"))
      (node (ref "U1") (pin "P$78") (pinfunction "VSS_PAD_P$78") (pintype "bidirectional"))
      (node (ref "U1") (pin "P$79") (pinfunction "VSS_PAD_P$79") (pintype "bidirectional"))
      (node (ref "U1") (pin "P$80") (pinfunction "VSS_PAD_P$80") (pintype "bidirectional"))
      (node (ref "U1") (pin "P$81") (pinfunction "VSS_PAD_P$81") (pintype "bidirectional"))
      (node (ref "U1") (pin "P$82") (pinfunction "VSS_PAD_P$82") (pintype "bidirectional"))
      (node (ref "U1") (pin "P$83") (pinfunction "VSS_PAD_P$83") (pintype "bidirectional"))
      (node (ref "U1") (pin "P$84") (pinfunction "VSS_PAD_P$84") (pintype "bidirectional"))
      (node (ref "U1") (pin "P$85") (pinfunction "VSS_PAD_P$85") (pintype "bidirectional"))
      (node (ref "U1") (pin "P$86") (pinfunction "VSS_PAD_P$86") (pintype "bidirectional"))
      (node (ref "U1") (pin "P$87") (pinfunction "VSS_PAD_P$87") (pintype "bidirectional"))
      (node (ref "U1") (pin "P$88") (pinfunction "VSS_PAD_P$88") (pintype "bidirectional"))
      (node (ref "U1") (pin "P$89") (pinfunction "VSS_PAD_P$89") (pintype "bidirectional"))
      (node (ref "U1") (pin "P$90") (pinfunction "VSS_PAD_P$90") (pintype "bidirectional"))
      (node (ref "U1") (pin "P$B7") (pinfunction "VSS_P$B7") (pintype "power_in"))
      (node (ref "U1") (pin "P$F23") (pinfunction "VSS_PA_P$F23") (pintype "bidirectional"))
      (node (ref "U3") (pin "1") (pinfunction "CTG_1") (pintype "power_in"))
      (node (ref "U3") (pin "4") (pinfunction "GND_4") (pintype "power_in"))
      (node (ref "U3") (pin "6") (pinfunction "QSTRT_6") (pintype "input"))
      (node (ref "U3") (pin "9") (pinfunction "EP_9") (pintype "power_in"))
      (node (ref "X1") (pin "2") (pinfunction "2_2") (pintype "passive"))
      (node (ref "X1") (pin "4") (pinfunction "4_4") (pintype "passive"))
    )
    (net (code "22") (name "HAPTIC_EN{slash}1.4A") (class "Default")
      (node (ref "IC2") (pin "A1") (pinfunction "EN_A1") (pintype "bidirectional"))
    )
    (net (code "23") (name "HAPTIC_EN{slash}2.6A") (class "Default")
      (node (ref "U1") (pin "P$U1") (pinfunction "P0.12_P$U1") (pintype "bidirectional"))
    )
    (net (code "24") (name "IMU_INT1") (class "Default")
      (node (ref "IC3") (pin "5") (pinfunction "INT1_5") (pintype "bidirectional"))
      (node (ref "U1") (pin "P$N1") (pinfunction "P0.08_P$N1") (pintype "bidirectional"))
    )
    (net (code "25") (name "IMU_INT2") (class "Default")
      (node (ref "IC3") (pin "6") (pinfunction "INT2_6") (pintype "bidirectional"))
      (node (ref "U1") (pin "P$P2") (pinfunction "P1.08_P$P2") (pintype "bidirectional"))
    )
    (net (code "26") (name "LX1") (class "Default")
      (node (ref "IC9") (pin "B2") (pinfunction "SW1_1_B2") (pintype "bidirectional"))
      (node (ref "IC9") (pin "B3") (pinfunction "SW1_2_B3") (pintype "bidirectional"))
      (node (ref "L7") (pin "1") (pinfunction "1_1") (pintype "bidirectional"))
    )
    (net (code "27") (name "LX2") (class "Default")
      (node (ref "IC9") (pin "D2") (pinfunction "SW2_1_D2") (pintype "bidirectional"))
      (node (ref "IC9") (pin "D3") (pinfunction "SW2_2_D3") (pintype "bidirectional"))
      (node (ref "L7") (pin "2") (pinfunction "2_2") (pintype "bidirectional"))
    )
    (net (code "28") (name "MOSI{slash}1.5B") (class "Default")
      (node (ref "J1") (pin "14") (pinfunction "14_14") (pintype "bidirectional"))
    )
    (net (code "29") (name "MOSI{slash}2.2D") (class "Default")
      (node (ref "U1") (pin "P$B13") (pinfunction "P0.03/AIN1_P$B13") (pintype "bidirectional"))
    )
    (net (code "30") (name "Net-(ANT1-FEED)") (class "Default")
      (node (ref "ANT1") (pin "1") (pinfunction "FEED_1") (pintype "input"))
      (node (ref "C22") (pin "1") (pinfunction "1_1") (pintype "passive"))
      (node (ref "C4") (pin "1") (pinfunction "1_1") (pintype "passive"))
      (node (ref "L1") (pin "2") (pinfunction "2_2") (pintype "passive"))
    )
    (net (code "31") (name "Net-(D2-A)") (class "Default")
      (node (ref "C2-EP-DR1") (pin "1") (pinfunction "1_1") (pintype "passive"))
      (node (ref "D2") (pin "2") (pinfunction "A_2") (pintype "bidirectional"))
      (node (ref "D4") (pin "1") (pinfunction "K_1") (pintype "bidirectional"))
    )
    (net (code "32") (name "Net-(D5-A)") (class "Default")
      (node (ref "C2-EP-DR1") (pin "2") (pinfunction "2_2") (pintype "passive"))
      (node (ref "D5") (pin "2") (pinfunction "A_2") (pintype "bidirectional"))
      (node (ref "L5") (pin "1") (pinfunction "1_1") (pintype "passive"))
      (node (ref "Q3") (pin "3") (pinfunction "D_3") (pintype "bidirectional"))
    )
    (net (code "33") (name "Net-(EPD_C1-Pad2)") (class "Default")
      (node (ref "EPD_C1") (pin "2") (pinfunction "2_2") (pintype "passive"))
      (node (ref "J1") (pin "5") (pinfunction "5_5") (pintype "bidirectional"))
    )
    (net (code "34") (name "Net-(EPD_C2-Pad2)") (class "Default")
      (node (ref "EPD_C2") (pin "2") (pinfunction "2_2") (pintype "passive"))
      (node (ref "J1") (pin "4") (pinfunction "4_4") (pintype "bidirectional"))
    )
    (net (code "35") (name "Net-(EPD_C6-Pad2)") (class "Default")
      (node (ref "EPD_C6") (pin "2") (pinfunction "2_2") (pintype "passive"))
      (node (ref "J1") (pin "18") (pinfunction "18_18") (pintype "bidirectional"))
    )
    (net (code "36") (name "Net-(EPD_C7-Pad2)") (class "Default")
      (node (ref "EPD_C7") (pin "2") (pinfunction "2_2") (pintype "passive"))
      (node (ref "J1") (pin "19") (pinfunction "19_19") (pintype "bidirectional"))
    )
    (net (code "37") (name "Net-(EPD_C8-Pad2)") (class "Default")
      (node (ref "EPD_C8") (pin "2") (pinfunction "2_2") (pintype "passive"))
      (node (ref "J1") (pin "20") (pinfunction "20_20") (pintype "bidirectional"))
    )
    (net (code "38") (name "Net-(EPD_C11-Pad2)") (class "Default")
      (node (ref "EPD_C11") (pin "2") (pinfunction "2_2") (pintype "passive"))
      (node (ref "J1") (pin "23") (pinfunction "23_23") (pintype "bidirectional"))
    )
    (net (code "39") (name "Net-(EPD_C12-Pad2)") (class "Default")
      (node (ref "EPD_C12") (pin "2") (pinfunction "2_2") (pintype "passive"))
      (node (ref "J1") (pin "24") (pinfunction "24_24") (pintype "bidirectional"))
    )
    (net (code "40") (name "Net-(IC1-TS{slash}MR)") (class "Default")
      (node (ref "IC1") (pin "D1") (pinfunction "TS/MR_D1") (pintype "bidirectional"))
      (node (ref "R9") (pin "2") (pinfunction "2_2") (pintype "bidirectional"))
    )
    (net (code "41") (name "Net-(IC2-REG)") (class "Default")
      (node (ref "C32") (pin "2") (pinfunction "2_2") (pintype "passive"))
      (node (ref "IC2") (pin "A2") (pinfunction "REG_A2") (pintype "bidirectional"))
    )
    (net (code "42") (name "Net-(IC3-SDO)") (class "Default")
      (node (ref "IC3") (pin "1") (pinfunction "SDO_1") (pintype "bidirectional"))
      (node (ref "R3") (pin "2") (pinfunction "2_2") (pintype "bidirectional"))
    )
    (net (code "43") (name "Net-(IC9-SCL)") (class "Default")
      (node (ref "IC9") (pin "D1") (pinfunction "SCL_D1") (pintype "bidirectional"))
      (node (ref "R4") (pin "2") (pinfunction "2_2") (pintype "bidirectional"))
    )
    (net (code "44") (name "Net-(IC9-SDA)") (class "Default")
      (node (ref "IC9") (pin "E1") (pinfunction "SDA_E1") (pintype "bidirectional"))
      (node (ref "R2") (pin "2") (pinfunction "2_2") (pintype "bidirectional"))
    )
    (net (code "45") (name "Net-(J4-CC1)") (class "Default")
      (node (ref "J4") (pin "A5") (pinfunction "CC1_A5") (pintype "bidirectional"))
      (node (ref "R1_USB") (pin "2") (pinfunction "2_2") (pintype "bidirectional"))
    )
    (net (code "46") (name "Net-(J4-CC2)") (class "Default")
      (node (ref "J4") (pin "B5") (pinfunction "CC2_B5") (pintype "bidirectional"))
      (node (ref "R2_USB") (pin "1") (pinfunction "1_1") (pintype "bidirectional"))
    )
    (net (code "47") (name "Net-(L2-Pad1)") (class "Default")
      (node (ref "L2") (pin "1") (pinfunction "1_1") (pintype "passive"))
      (node (ref "L3") (pin "2") (pinfunction "2_2") (pintype "passive"))
    )
    (net (code "48") (name "Net-(R1_EP_DR-Pad1)") (class "Default")
      (node (ref "R1_EP_DR") (pin "1") (pinfunction "1_1") (pintype "bidirectional"))
      (node (ref "R_TYPE_SEL") (pin "2") (pinfunction "2_2") (pintype "bidirectional"))
      (node (ref "SJ1") (pin "2") (pinfunction "2_2") (pintype "passive"))
    )
    (net (code "49") (name "Net-(U1-ANT)") (class "Default")
      (node (ref "C3") (pin "1") (pinfunction "1_1") (pintype "passive"))
      (node (ref "L1") (pin "1") (pinfunction "1_1") (pintype "passive"))
      (node (ref "U1") (pin "P$H23") (pinfunction "ANT_P$H23") (pintype "bidirectional"))
    )
    (net (code "50") (name "Net-(U1-DCC)") (class "Default")
      (node (ref "L2") (pin "2") (pinfunction "2_2") (pintype "passive"))
      (node (ref "U1") (pin "P$B3") (pinfunction "DCC_P$B3") (pintype "output"))
    )
    (net (code "51") (name "Net-(U1-DEC1)") (class "Default")
      (node (ref "C5") (pin "1") (pinfunction "1_1") (pintype "passive"))
      (node (ref "U1") (pin "P$C1") (pinfunction "DEC1_P$C1") (pintype "power_in"))
    )
    (net (code "52") (name "Net-(U1-DEC2)") (class "Default")
      (node (ref "C13") (pin "2") (pinfunction "2_2") (pintype "passive"))
      (node (ref "U1") (pin "P$A18") (pinfunction "DEC2_P$A18") (pintype "bidirectional"))
    )
    (net (code "53") (name "Net-(U1-DEC3)") (class "Default")
      (node (ref "C11") (pin "1") (pinfunction "1_1") (pintype "passive"))
      (node (ref "U1") (pin "P$D23") (pinfunction "DEC3_P$D23") (pintype "bidirectional"))
    )
    (net (code "54") (name "Net-(U1-DEC3V3)") (class "Default")
      (node (ref "C20") (pin "1") (pinfunction "1_1") (pintype "passive"))
      (node (ref "U1") (pin "P$AC5") (pinfunction "DEC3V3_P$AC5") (pintype "bidirectional"))
    )
    (net (code "55") (name "Net-(U1-DEC4)") (class "Default")
      (node (ref "C10") (pin "2") (pinfunction "2_2") (pintype "passive"))
      (node (ref "C15") (pin "1") (pinfunction "1_1") (pintype "passive"))
      (node (ref "C16") (pin "1") (pinfunction "1_1") (pintype "passive"))
      (node (ref "L3") (pin "1") (pinfunction "1_1") (pintype "passive"))
      (node (ref "U1") (pin "P$B5") (pinfunction "DEC4_P$B5") (pintype "power_in"))
      (node (ref "U1") (pin "P$E24") (pinfunction "DEC6_P$E24") (pintype "bidirectional"))
    )
    (net (code "56") (name "Net-(U1-DEC5)") (class "Default")
      (node (ref "C9") (pin "1") (pinfunction "1_1") (pintype "passive"))
      (node (ref "U1") (pin "P$N24") (pinfunction "DEC5_P$N24") (pintype "bidirectional"))
    )
    (net (code "57") (name "Net-(U1-P0.00{slash}XL1)") (class "Default")
      (node (ref "C17") (pin "2") (pinfunction "2_2") (pintype "passive"))
      (node (ref "U1") (pin "P$D2") (pinfunction "P0.00/XL1_P$D2") (pintype "bidirectional"))
      (node (ref "X2") (pin "2") (pinfunction "2_2") (pintype "passive"))
    )
    (net (code "58") (name "Net-(U1-P0.01{slash}XL2)") (class "Default")
      (node (ref "C18") (pin "2") (pinfunction "2_2") (pintype "passive"))
      (node (ref "U1") (pin "P$F2") (pinfunction "P0.01/XL2_P$F2") (pintype "bidirectional"))
      (node (ref "X2") (pin "1") (pinfunction "1_1") (pintype "passive"))
    )
    (net (code "59") (name "Net-(U1-XC1)") (class "Default")
      (node (ref "C1") (pin "1") (pinfunction "1_1") (pintype "passive"))
      (node (ref "U1") (pin "P$B24") (pinfunction "XC1_P$B24") (pintype "input"))
      (node (ref "X1") (pin "1") (pinfunction "1_1") (pintype "passive"))
    )
    (net (code "60") (name "Net-(U1-XC2)") (class "Default")
      (node (ref "C2") (pin "1") (pinfunction "1_1") (pintype "passive"))
      (node (ref "U1") (pin "P$A23") (pinfunction "XC2_P$A23") (pintype "output"))
      (node (ref "X1") (pin "3") (pinfunction "3_3") (pintype "passive"))
    )
    (net (code "61") (name "OUT+") (class "Default")
      (node (ref "IC2") (pin "A3") (pinfunction "OUT+_A3") (pintype "bidirectional"))
      (node (ref "TP_OP") (pin "TP") (pinfunction "TP_TP") (pintype "input"))
    )
    (net (code "62") (name "OUT-") (class "Default")
      (node (ref "IC2") (pin "C3") (pinfunction "OUT-_C3") (pintype "bidirectional"))
      (node (ref "TP_ON") (pin "TP") (pinfunction "TP_TP") (pintype "input"))
    )
    (net (code "63") (name "P0.04") (class "Default")
      (node (ref "U1") (pin "P$J1") (pinfunction "P0.04/AIN2_P$J1") (pintype "bidirectional"))
    )
    (net (code "64") (name "P0.09") (class "Default")
      (node (ref "U1") (pin "P$L24") (pinfunction "P0.09/NFC1_P$L24") (pintype "bidirectional"))
    )
    (net (code "65") (name "P0.13{slash}1.5D") (class "Default")
      (node (ref "C30") (pin "1") (pinfunction "1_1") (pintype "passive"))
      (node (ref "R5") (pin "1") (pinfunction "1_1") (pintype "bidirectional"))
      (node (ref "SW_UP") (pin "2") (pinfunction "2_2") (pintype "passive"))
    )
    (net (code "66") (name "P0.13{slash}2.6C") (class "Default")
      (node (ref "U1") (pin "P$AD8") (pinfunction "P0.13_P$AD8") (pintype "bidirectional"))
    )
    (net (code "67") (name "P0.14{slash}1.5D") (class "Default")
      (node (ref "C31") (pin "1") (pinfunction "1_1") (pintype "passive"))
      (node (ref "R8") (pin "1") (pinfunction "1_1") (pintype "bidirectional"))
      (node (ref "SW_ENT") (pin "2") (pinfunction "2_2") (pintype "passive"))
    )
    (net (code "68") (name "P0.14{slash}2.7C") (class "Default")
      (node (ref "U1") (pin "P$AC9") (pinfunction "P0.14_P$AC9") (pintype "bidirectional"))
    )
    (net (code "69") (name "P0.19") (class "Default")
      (node (ref "U1") (pin "P$AC15") (pinfunction "P0.19_P$AC15") (pintype "bidirectional"))
    )
    (net (code "70") (name "P0.20") (class "Default")
      (node (ref "U1") (pin "P$AD16") (pinfunction "P0.20_P$AD16") (pintype "bidirectional"))
    )
    (net (code "71") (name "P0.21") (class "Default")
      (node (ref "U1") (pin "P$AC17") (pinfunction "P0.21_P$AC17") (pintype "bidirectional"))
    )
    (net (code "72") (name "P0.22") (class "Default")
      (node (ref "U1") (pin "P$AD18") (pinfunction "P0.22_P$AD18") (pintype "bidirectional"))
    )
    (net (code "73") (name "P0.23") (class "Default")
      (node (ref "U1") (pin "P$AC19") (pinfunction "P0.23_P$AC19") (pintype "bidirectional"))
    )
    (net (code "74") (name "P0.24") (class "Default")
      (node (ref "U1") (pin "P$AD20") (pinfunction "P0.24_P$AD20") (pintype "bidirectional"))
    )
    (net (code "75") (name "P0.25") (class "Default")
      (node (ref "U1") (pin "P$AC21") (pinfunction "P0.25_P$AC21") (pintype "bidirectional"))
    )
    (net (code "76") (name "P0.26") (class "Default")
      (node (ref "U1") (pin "P$G1") (pinfunction "P0.26_P$G1") (pintype "bidirectional"))
    )
    (net (code "77") (name "P0.27") (class "Default")
      (node (ref "U1") (pin "P$H2") (pinfunction "P0.27_P$H2") (pintype "bidirectional"))
    )
    (net (code "78") (name "P0.28") (class "Default")
      (node (ref "U1") (pin "P$B11") (pinfunction "P0.28/AIN4_P$B11") (pintype "bidirectional"))
    )
    (net (code "79") (name "P0.29") (class "Default")
      (node (ref "U1") (pin "P$A10") (pinfunction "P0.29/AIN5_P$A10") (pintype "bidirectional"))
    )
    (net (code "80") (name "P0.30") (class "Default")
      (node (ref "U1") (pin "P$B9") (pinfunction "P0.30/AIN6_P$B9") (pintype "bidirectional"))
    )
    (net (code "81") (name "P0.31") (class "Default")
      (node (ref "U1") (pin "P$A8") (pinfunction "P0.31/AIN7_P$A8") (pintype "bidirectional"))
    )
    (net (code "82") (name "P1.01{slash}1.6C") (class "Default")
      (node (ref "Q1") (pin "1") (pinfunction "G_1") (pintype "bidirectional"))
      (node (ref "R_PWR_EPD") (pin "1") (pinfunction "1_1") (pintype "bidirectional"))
    )
    (net (code "83") (name "P1.01{slash}2.4B") (class "Default")
      (node (ref "U1") (pin "P$Y23") (pinfunction "P1.01_P$Y23") (pintype "bidirectional"))
    )
    (net (code "84") (name "P1.02{slash}1.6C") (class "Default")
      (node (ref "C29") (pin "1") (pinfunction "1_1") (pintype "passive"))
      (node (ref "R7") (pin "1") (pinfunction "1_1") (pintype "bidirectional"))
      (node (ref "SW_DN") (pin "2") (pinfunction "2_2") (pintype "passive"))
    )
    (net (code "85") (name "P1.02{slash}2.8C") (class "Default")
      (node (ref "U1") (pin "P$W24") (pinfunction "P1.02_P$W24") (pintype "bidirectional"))
    )
    (net (code "86") (name "P1.03") (class "Default")
      (node (ref "U1") (pin "P$V23") (pinfunction "P1.03_P$V23") (pintype "bidirectional"))
    )
    (net (code "87") (name "P1.04") (class "Default")
      (node (ref "U1") (pin "P$U24") (pinfunction "P1.04_P$U24") (pintype "bidirectional"))
    )
    (net (code "88") (name "P1.05") (class "Default")
      (node (ref "U1") (pin "P$T23") (pinfunction "P1.05_P$T23") (pintype "bidirectional"))
    )
    (net (code "89") (name "P1.06") (class "Default")
      (node (ref "U1") (pin "P$R24") (pinfunction "P1.06_P$R24") (pintype "bidirectional"))
    )
    (net (code "90") (name "P1.07") (class "Default")
      (node (ref "U1") (pin "P$P23") (pinfunction "P1.07_P$P23") (pintype "bidirectional"))
    )
    (net (code "91") (name "P1.09") (class "Default")
      (node (ref "U1") (pin "P$R1") (pinfunction "P1.09_P$R1") (pintype "bidirectional"))
    )
    (net (code "92") (name "P1.10") (class "Default")
      (node (ref "U1") (pin "P$A20") (pinfunction "P1.10_P$A20") (pintype "bidirectional"))
    )
    (net (code "93") (name "P1.11") (class "Default")
      (node (ref "U1") (pin "P$B19") (pinfunction "P1.11_P$B19") (pintype "bidirectional"))
    )
    (net (code "94") (name "P1.12") (class "Default")
      (node (ref "U1") (pin "P$B17") (pinfunction "P1.12_P$B17") (pintype "bidirectional"))
    )
    (net (code "95") (name "P1.13") (class "Default")
      (node (ref "U1") (pin "P$A16") (pinfunction "P1.13_P$A16") (pintype "bidirectional"))
    )
    (net (code "96") (name "P1.14") (class "Default")
      (node (ref "U1") (pin "P$B15") (pinfunction "P1.14_P$B15") (pintype "bidirectional"))
    )
    (net (code "97") (name "P1.15") (class "Default")
      (node (ref "U1") (pin "P$A14") (pinfunction "P1.15_P$A14") (pintype "bidirectional"))
    )
    (net (code "98") (name "PMIC_INT") (class "Default")
      (node (ref "IC1") (pin "A1") (pinfunction "~{INT}_A1") (pintype "bidirectional"))
      (node (ref "U1") (pin "P$T2") (pinfunction "P0.11_P$T2") (pintype "bidirectional"))
    )
    (net (code "99") (name "PREVGH") (class "Default")
      (node (ref "D5") (pin "1") (pinfunction "K_1") (pintype "bidirectional"))
      (node (ref "EPD_C9") (pin "2") (pinfunction "2_2") (pintype "passive"))
      (node (ref "J1") (pin "21") (pinfunction "21_21") (pintype "bidirectional"))
    )
    (net (code "100") (name "PREVGL") (class "Default")
      (node (ref "D4") (pin "2") (pinfunction "A_2") (pintype "bidirectional"))
      (node (ref "EPD_C10") (pin "2") (pinfunction "2_2") (pintype "passive"))
      (node (ref "J1") (pin "22") (pinfunction "22_22") (pintype "bidirectional"))
    )
    (net (code "101") (name "RESE") (class "Default")
      (node (ref "J1") (pin "3") (pinfunction "3_3") (pintype "bidirectional"))
      (node (ref "Q3") (pin "2") (pinfunction "S_2") (pintype "bidirectional"))
      (node (ref "R1_EP_DR") (pin "2") (pinfunction "2_2") (pintype "bidirectional"))
    )
    (net (code "102") (name "RESET") (class "Default")
      (node (ref "J2") (pin "6") (pinfunction "6_6") (pintype "bidirectional"))
      (node (ref "TP4") (pin "TP") (pinfunction "TP_TP") (pintype "input"))
      (node (ref "U1") (pin "P$AC13") (pinfunction "P0.18/RESET_P$AC13") (pintype "bidirectional"))
    )
    (net (code "103") (name "SCK{slash}1.5B") (class "Default")
      (node (ref "J1") (pin "13") (pinfunction "13_13") (pintype "bidirectional"))
    )
    (net (code "104") (name "SCK{slash}2.2D") (class "Default")
      (node (ref "U1") (pin "P$A12") (pinfunction "P0.02/AIN0_P$A12") (pintype "bidirectional"))
    )
    (net (code "105") (name "SCL{slash}1.4C") (class "Default")
      (node (ref "IC2") (pin "C1") (pinfunction "SCL_C1") (pintype "bidirectional"))
      (node (ref "U3") (pin "7") (pinfunction "SCL_7") (pintype "input"))
    )
    (net (code "106") (name "SCL{slash}2.4C") (class "Default")
      (node (ref "IC1") (pin "B1") (pinfunction "SCL_B1") (pintype "bidirectional"))
      (node (ref "IC3") (pin "12") (pinfunction "SCX_12") (pintype "bidirectional"))
      (node (ref "R17") (pin "2") (pinfunction "2_2") (pintype "bidirectional"))
      (node (ref "R4") (pin "1") (pinfunction "1_1") (pintype "bidirectional"))
      (node (ref "TP_SCL") (pin "TP") (pinfunction "TP_TP") (pintype "input"))
      (node (ref "U1") (pin "P$M2") (pinfunction "P0.07_P$M2") (pintype "bidirectional"))
    )
    (net (code "107") (name "SDA{slash}1.4C") (class "Default")
      (node (ref "IC2") (pin "B2") (pinfunction "SDA_B2") (pintype "bidirectional"))
      (node (ref "U3") (pin "8") (pinfunction "SDA_8") (pintype "bidirectional"))
    )
    (net (code "108") (name "SDA{slash}2.4C") (class "Default")
      (node (ref "IC1") (pin "C1") (pinfunction "SDA_C1") (pintype "bidirectional"))
      (node (ref "IC3") (pin "2") (pinfunction "SDX_2") (pintype "bidirectional"))
      (node (ref "R18") (pin "2") (pinfunction "2_2") (pintype "bidirectional"))
      (node (ref "R2") (pin "1") (pinfunction "1_1") (pintype "bidirectional"))
      (node (ref "TP_SDA") (pin "TP") (pinfunction "TP_TP") (pintype "input"))
      (node (ref "U1") (pin "P$L1") (pinfunction "P0.06_P$L1") (pintype "bidirectional"))
    )
    (net (code "109") (name "SWDCLK") (class "Default")
      (node (ref "J2") (pin "4") (pinfunction "4_4") (pintype "bidirectional"))
      (node (ref "TP3") (pin "TP") (pinfunction "TP_TP") (pintype "input"))
      (node (ref "U1") (pin "P$AA24") (pinfunction "SWDCLK_P$AA24") (pintype "input"))
    )
    (net (code "110") (name "SWDIO") (class "Default")
      (node (ref "J2") (pin "2") (pinfunction "2_2") (pintype "bidirectional"))
      (node (ref "TP2") (pin "TP") (pinfunction "TP_TP") (pintype "input"))
      (node (ref "U1") (pin "P$AC24") (pinfunction "SWDIO_P$AC24") (pintype "bidirectional"))
    )
    (net (code "111") (name "SWO") (class "Default")
      (node (ref "TP1") (pin "TP") (pinfunction "TP_TP") (pintype "input"))
      (node (ref "U1") (pin "P$AD22") (pinfunction "P1.00_P$AD22") (pintype "bidirectional"))
    )
    (net (code "112") (name "VBAT{slash}1.2A") (class "Default")
      (node (ref "C27") (pin "1") (pinfunction "1_1") (pintype "passive"))
      (node (ref "TP_VBAT") (pin "TP") (pinfunction "TP_TP") (pintype "input"))
      (node (ref "U3") (pin "2") (pinfunction "CELL_2") (pintype "power_in"))
      (node (ref "U3") (pin "3") (pinfunction "VDD_3") (pintype "power_in"))
    )
    (net (code "113") (name "VBAT{slash}2.5C") (class "Default")
      (node (ref "C37") (pin "2") (pinfunction "2_2") (pintype "passive"))
      (node (ref "IC1") (pin "C2") (pinfunction "BAT_C2") (pintype "bidirectional"))
    )
    (net (code "114") (name "VBUS{slash}1.5D") (class "Default")
      (node (ref "C42") (pin "1") (pinfunction "1_1") (pintype "passive"))
      (node (ref "C43") (pin "1") (pinfunction "1_1") (pintype "passive"))
      (node (ref "D3") (pin "5") (pinfunction "VBUS_5") (pintype "bidirectional"))
      (node (ref "J4") (pin "A4_B9") (pinfunction "VBUS_A4_B9") (pintype "power_in"))
      (node (ref "J4") (pin "A9_B4") (pinfunction "VBUS_A9_B4") (pintype "power_in"))
    )
    (net (code "115") (name "VBUS{slash}2.6D") (class "Default")
      (node (ref "C21") (pin "1") (pinfunction "1_1") (pintype "passive"))
      (node (ref "C38") (pin "2") (pinfunction "2_2") (pintype "passive"))
      (node (ref "IC1") (pin "A2") (pinfunction "IN_A2") (pintype "bidirectional"))
      (node (ref "U1") (pin "P$AD2") (pinfunction "VBUS_P$AD2") (pintype "power_in"))
    )
    (net (code "116") (name "VREG") (class "Default")
      (node (ref "C23") (pin "2") (pinfunction "2_2") (pintype "passive"))
      (node (ref "C24") (pin "2") (pinfunction "2_2") (pintype "passive"))
      (node (ref "C39") (pin "1") (pinfunction "1_1") (pintype "passive"))
      (node (ref "IC1") (pin "B2") (pinfunction "SYS_B2") (pintype "bidirectional"))
      (node (ref "IC9") (pin "A1") (pinfunction "EN_A1") (pintype "bidirectional"))
      (node (ref "IC9") (pin "A2") (pinfunction "VIN_1_A2") (pintype "bidirectional"))
      (node (ref "IC9") (pin "A3") (pinfunction "VIN_2_A3") (pintype "bidirectional"))
      (node (ref "TP_VREG") (pin "TP") (pinfunction "TP_TP") (pintype "input"))
    )
    (net (code "117") (name "unconnected-(ANT1-NC-Pad2)") (class "Default")
      (node (ref "ANT1") (pin "2") (pinfunction "NC_2") (pintype "no_connect"))
    )
    (net (code "118") (name "unconnected-(IC3-ASCL-Pad11)") (class "Default")
      (node (ref "IC3") (pin "11") (pinfunction "ASCL_11") (pintype "bidirectional"))
    )
    (net (code "119") (name "unconnected-(IC3-ASDA-Pad4)") (class "Default")
      (node (ref "IC3") (pin "4") (pinfunction "ASDA_4") (pintype "bidirectional"))
    )
    (net (code "120") (name "unconnected-(J1-Pad1)") (class "Default")
      (node (ref "J1") (pin "1") (pinfunction "1_1") (pintype "bidirectional"))
    )
    (net (code "121") (name "unconnected-(J1-Pad6)") (class "Default")
      (node (ref "J1") (pin "6") (pinfunction "6_6") (pintype "bidirectional"))
    )
    (net (code "122") (name "unconnected-(J1-Pad7)") (class "Default")
      (node (ref "J1") (pin "7") (pinfunction "7_7") (pintype "bidirectional"))
    )
    (net (code "123") (name "unconnected-(J4-SBU1-PadA8)") (class "Default")
      (node (ref "J4") (pin "A8") (pinfunction "SBU1_A8") (pintype "bidirectional"))
    )
    (net (code "124") (name "unconnected-(J4-SBU2-PadB8)") (class "Default")
      (node (ref "J4") (pin "B8") (pinfunction "SBU2_B8") (pintype "bidirectional"))
    )
    (net (code "125") (name "unconnected-(U1-DCCH-PadP$AB2)") (class "Default")
      (node (ref "U1") (pin "P$AB2") (pinfunction "DCCH_P$AB2") (pintype "bidirectional"))
    )
  )
)
